# babyNamer.net
KiCad netlist of a schematic drawn in EAGLE
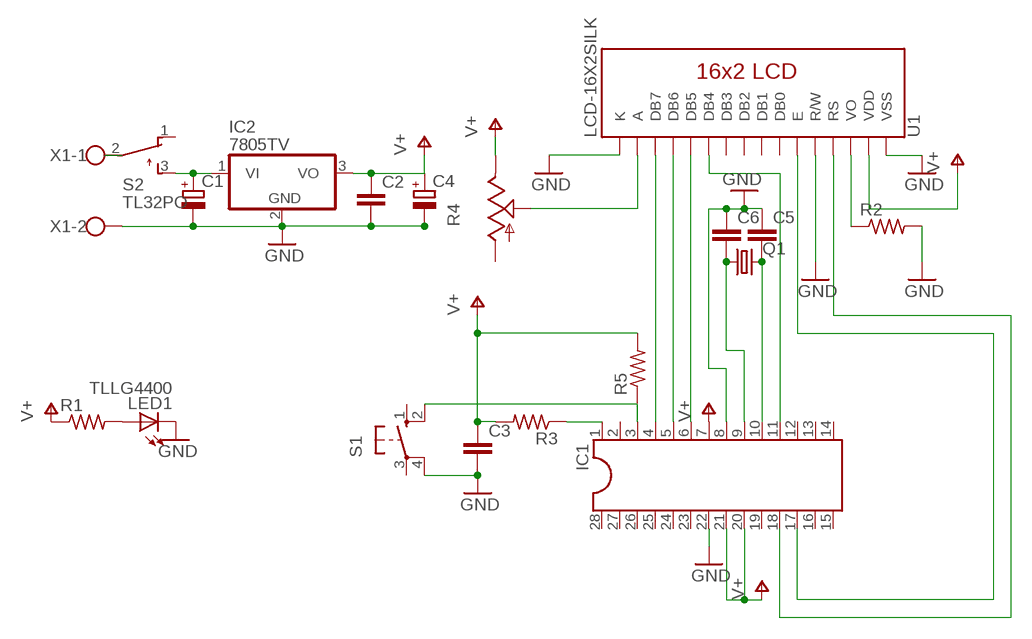
[diagram p0: schematic, sheet 1]

(export (version "E")
  (design (tool "Eeschema 10.0.6"))
  (components
    (comp (ref "C1")
      (value "CPOL-EUE3.5-8")
      (footprint "eagle-import:E3,5-8")
      (libsource (lib "eagle-import") (part "CPOL-EUE3.5-8"))
    )
    (comp (ref "C2")
      (value "C-EU050-024X044")
      (footprint "eagle-import:C050-024X044")
      (libsource (lib "eagle-import") (part "C-EU050-024X044"))
    )
    (comp (ref "C3")
      (value "C-EU050-024X044")
      (footprint "eagle-import:C050-024X044")
      (libsource (lib "eagle-import") (part "C-EU050-024X044"))
    )
    (comp (ref "C4")
      (value "CPOL-EUE3.5-8")
      (footprint "eagle-import:E3,5-8")
      (libsource (lib "eagle-import") (part "CPOL-EUE3.5-8"))
    )
    (comp (ref "C5")
      (value "C-EU050-024X044")
      (footprint "eagle-import:C050-024X044")
      (libsource (lib "eagle-import") (part "C-EU050-024X044"))
    )
    (comp (ref "C6")
      (value "C-EU050-024X044")
      (footprint "eagle-import:C050-024X044")
      (libsource (lib "eagle-import") (part "C-EU050-024X044"))
    )
    (comp (ref "IC1")
      (value "DIL28-3")
      (footprint "eagle-import:DIL28-3")
      (libsource (lib "eagle-import") (part "DIL28-3"))
    )
    (comp (ref "IC2")
      (value "7805TV")
      (footprint "eagle-import:TO220V")
      (libsource (lib "eagle-import") (part "78TV05"))
    )
    (comp (ref "LED1")
      (value "TLLG4400")
      (footprint "eagle-import:LED3MM")
      (fields (field (name "MF") "VISHAY SEMICONDUCTOR"))
      (libsource (lib "eagle-import") (part "TLLG4400"))
    )
    (comp (ref "Q1")
      (value "CRYSTALHC49US")
      (footprint "eagle-import:HC49US")
      (libsource (lib "eagle-import") (part "CRYSTALHC49US"))
    )
    (comp (ref "R1")
      (value "R-US_0204/7")
      (footprint "eagle-import:0204_7")
      (libsource (lib "eagle-import") (part "R-US_0204/7"))
    )
    (comp (ref "R2")
      (value "R-US_0204/7")
      (footprint "eagle-import:0204_7")
      (libsource (lib "eagle-import") (part "R-US_0204/7"))
    )
    (comp (ref "R3")
      (value "R-US_0204/7")
      (footprint "eagle-import:0204_7")
      (libsource (lib "eagle-import") (part "R-US_0204/7"))
    )
    (comp (ref "R4")
      (value "TRIM_US-CA9V")
      (footprint "eagle-import:CA9V")
      (libsource (lib "eagle-import") (part "TRIM_US-CA9V"))
    )
    (comp (ref "R5")
      (value "R-US_0204/7")
      (footprint "eagle-import:0204_7")
      (libsource (lib "eagle-import") (part "R-US_0204/7"))
    )
    (comp (ref "S1")
      (value "10-XX")
      (footprint "eagle-import:B3F-10XX")
      (fields (field (name "MPN") "B3F-1000"))
      (libsource (lib "eagle-import") (part "10-XX"))
    )
    (comp (ref "S2")
      (value "TL32PO")
      (footprint "eagle-import:TL3XPO")
      (libsource (lib "eagle-import") (part "TL32PO"))
    )
    (comp (ref "U1")
      (value "LCD-16X2SILK")
      (footprint "eagle-import:LCD-16X2")
      (libsource (lib "eagle-import") (part "LCD-16X2SILK"))
    )
    (comp (ref "X1")
      (value "W237-102")
      (footprint "eagle-import:W237-102")
      (fields (field (name "MPN") "237-102"))
      (libsource (lib "eagle-import") (part "W237-102"))
    )
  )
  (nets
    (net (code "1") (name "GND") (class "Default")
      (node (ref "C1") (pin "-") (pinfunction "-_-") (pintype "passive"))
      (node (ref "C2") (pin "2") (pinfunction "2_2") (pintype "passive"))
      (node (ref "C3") (pin "2") (pinfunction "2_2") (pintype "passive"))
      (node (ref "C4") (pin "-") (pinfunction "-_-") (pintype "passive"))
      (node (ref "C5") (pin "1") (pinfunction "1_1") (pintype "passive"))
      (node (ref "C6") (pin "1") (pinfunction "1_1") (pintype "passive"))
      (node (ref "IC1") (pin "22") (pinfunction "22_22") (pintype "passive"))
      (node (ref "IC1") (pin "8") (pinfunction "8_8") (pintype "passive"))
      (node (ref "IC2") (pin "2") (pinfunction "GND_2") (pintype "passive"))
      (node (ref "LED1") (pin "K") (pinfunction "C_K") (pintype "passive"))
      (node (ref "R2") (pin "2") (pinfunction "2_2") (pintype "passive"))
      (node (ref "S1") (pin "4") (pinfunction "P1_4") (pintype "passive"))
      (node (ref "U1") (pin "1") (pinfunction "VSS_1") (pintype "power_in"))
      (node (ref "U1") (pin "16") (pinfunction "K_16") (pintype "power_in"))
      (node (ref "U1") (pin "5") (pinfunction "R/W_5") (pintype "input"))
      (node (ref "X1") (pin "2") (pinfunction "KL_2") (pintype "passive"))
    )
    (net (code "2") (name "Net-(C5-Pad2)") (class "Default")
      (node (ref "C5") (pin "2") (pinfunction "2_2") (pintype "passive"))
      (node (ref "IC1") (pin "10") (pinfunction "10_10") (pintype "passive"))
      (node (ref "Q1") (pin "2") (pinfunction "2_2") (pintype "passive"))
    )
    (net (code "3") (name "Net-(C6-Pad2)") (class "Default")
      (node (ref "C6") (pin "2") (pinfunction "2_2") (pintype "passive"))
      (node (ref "IC1") (pin "9") (pinfunction "9_9") (pintype "passive"))
      (node (ref "Q1") (pin "1") (pinfunction "1_1") (pintype "passive"))
    )
    (net (code "4") (name "Net-(IC1-Pad1)") (class "Default")
      (node (ref "IC1") (pin "1") (pinfunction "1_1") (pintype "passive"))
      (node (ref "R3") (pin "1") (pinfunction "1_1") (pintype "passive"))
    )
    (net (code "5") (name "Net-(IC2-VI)") (class "Default")
      (node (ref "C1") (pin "+") (pinfunction "+_+") (pintype "passive"))
      (node (ref "IC2") (pin "1") (pinfunction "VI_1") (pintype "input"))
      (node (ref "S2") (pin "3") (pinfunction "S_3") (pintype "passive"))
    )
    (net (code "6") (name "Net-(LED1-PadA)") (class "Default")
      (node (ref "LED1") (pin "A") (pinfunction "A_A") (pintype "passive"))
      (node (ref "R1") (pin "2") (pinfunction "2_2") (pintype "passive"))
    )
    (net (code "7") (name "Net-(S1-S1)") (class "Default")
      (node (ref "IC1") (pin "3") (pinfunction "3_3") (pintype "passive"))
      (node (ref "R5") (pin "1") (pinfunction "1_1") (pintype "passive"))
      (node (ref "S1") (pin "2") (pinfunction "S1_2") (pintype "passive"))
    )
    (net (code "8") (name "Net-(S2-P)") (class "Default")
      (node (ref "S2") (pin "2") (pinfunction "P_2") (pintype "passive"))
      (node (ref "X1") (pin "1") (pinfunction "KL_1") (pintype "passive"))
    )
    (net (code "9") (name "Net-(U1-A)") (class "Default")
      (node (ref "R4") (pin "S") (pinfunction "S_S") (pintype "passive"))
      (node (ref "U1") (pin "15") (pinfunction "A_15") (pintype "power_in"))
    )
    (net (code "10") (name "Net-(U1-DB4)") (class "Default")
      (node (ref "IC1") (pin "11") (pinfunction "11_11") (pintype "passive"))
      (node (ref "U1") (pin "11") (pinfunction "DB4_11") (pintype "bidirectional"))
    )
    (net (code "11") (name "Net-(U1-DB5)") (class "Default")
      (node (ref "IC1") (pin "6") (pinfunction "6_6") (pintype "passive"))
      (node (ref "U1") (pin "12") (pinfunction "DB5_12") (pintype "bidirectional"))
    )
    (net (code "12") (name "Net-(U1-DB6)") (class "Default")
      (node (ref "IC1") (pin "5") (pinfunction "5_5") (pintype "passive"))
      (node (ref "U1") (pin "13") (pinfunction "DB6_13") (pintype "bidirectional"))
    )
    (net (code "13") (name "Net-(U1-DB7)") (class "Default")
      (node (ref "IC1") (pin "4") (pinfunction "4_4") (pintype "passive"))
      (node (ref "U1") (pin "14") (pinfunction "DB7_14") (pintype "bidirectional"))
    )
    (net (code "14") (name "Net-(U1-E)") (class "Default")
      (node (ref "IC1") (pin "17") (pinfunction "17_17") (pintype "passive"))
      (node (ref "U1") (pin "6") (pinfunction "E_6") (pintype "input"))
    )
    (net (code "15") (name "Net-(U1-RS)") (class "Default")
      (node (ref "IC1") (pin "18") (pinfunction "18_18") (pintype "passive"))
      (node (ref "U1") (pin "4") (pinfunction "RS_4") (pintype "input"))
    )
    (net (code "16") (name "Net-(U1-VO)") (class "Default")
      (node (ref "R2") (pin "1") (pinfunction "1_1") (pintype "passive"))
      (node (ref "U1") (pin "3") (pinfunction "VO_3") (pintype "bidirectional"))
    )
    (net (code "17") (name "V+") (class "Default")
      (node (ref "C2") (pin "1") (pinfunction "1_1") (pintype "passive"))
      (node (ref "C3") (pin "1") (pinfunction "1_1") (pintype "passive"))
      (node (ref "C4") (pin "+") (pinfunction "+_+") (pintype "passive"))
      (node (ref "IC1") (pin "20") (pinfunction "20_20") (pintype "passive"))
      (node (ref "IC1") (pin "21") (pinfunction "21_21") (pintype "passive"))
      (node (ref "IC1") (pin "7") (pinfunction "7_7") (pintype "passive"))
      (node (ref "IC2") (pin "3") (pinfunction "VO_3") (pintype "passive"))
      (node (ref "R1") (pin "1") (pinfunction "1_1") (pintype "passive"))
      (node (ref "R3") (pin "2") (pinfunction "2_2") (pintype "passive"))
      (node (ref "R4") (pin "E") (pinfunction "E_E") (pintype "passive"))
      (node (ref "R5") (pin "2") (pinfunction "2_2") (pintype "passive"))
      (node (ref "U1") (pin "2") (pinfunction "VDD_2") (pintype "power_in"))
    )
    (net (code "18") (name "unconnected-(IC1-Pad2)") (class "Default")
      (node (ref "IC1") (pin "2") (pinfunction "2_2") (pintype "passive"))
    )
    (net (code "19") (name "unconnected-(IC1-Pad12)") (class "Default")
      (node (ref "IC1") (pin "12") (pinfunction "12_12") (pintype "passive"))
    )
    (net (code "20") (name "unconnected-(IC1-Pad13)") (class "Default")
      (node (ref "IC1") (pin "13") (pinfunction "13_13") (pintype "passive"))
    )
    (net (code "21") (name "unconnected-(IC1-Pad14)") (class "Default")
      (node (ref "IC1") (pin "14") (pinfunction "14_14") (pintype "passive"))
    )
    (net (code "22") (name "unconnected-(IC1-Pad15)") (class "Default")
      (node (ref "IC1") (pin "15") (pinfunction "15_15") (pintype "passive"))
    )
    (net (code "23") (name "unconnected-(IC1-Pad16)") (class "Default")
      (node (ref "IC1") (pin "16") (pinfunction "16_16") (pintype "passive"))
    )
    (net (code "24") (name "unconnected-(IC1-Pad19)") (class "Default")
      (node (ref "IC1") (pin "19") (pinfunction "19_19") (pintype "passive"))
    )
    (net (code "25") (name "unconnected-(IC1-Pad23)") (class "Default")
      (node (ref "IC1") (pin "23") (pinfunction "23_23") (pintype "passive"))
    )
    (net (code "26") (name "unconnected-(IC1-Pad24)") (class "Default")
      (node (ref "IC1") (pin "24") (pinfunction "24_24") (pintype "passive"))
    )
    (net (code "27") (name "unconnected-(IC1-Pad25)") (class "Default")
      (node (ref "IC1") (pin "25") (pinfunction "25_25") (pintype "passive"))
    )
    (net (code "28") (name "unconnected-(IC1-Pad26)") (class "Default")
      (node (ref "IC1") (pin "26") (pinfunction "26_26") (pintype "passive"))
    )
    (net (code "29") (name "unconnected-(IC1-Pad27)") (class "Default")
      (node (ref "IC1") (pin "27") (pinfunction "27_27") (pintype "passive"))
    )
    (net (code "30") (name "unconnected-(IC1-Pad28)") (class "Default")
      (node (ref "IC1") (pin "28") (pinfunction "28_28") (pintype "passive"))
    )
    (net (code "31") (name "unconnected-(R4-PadA)") (class "Default")
      (node (ref "R4") (pin "A") (pinfunction "A_A") (pintype "passive"))
    )
    (net (code "32") (name "unconnected-(S1-P-Pad3)") (class "Default")
      (node (ref "S1") (pin "3") (pinfunction "P_3") (pintype "passive"))
    )
    (net (code "33") (name "unconnected-(S1-S-Pad1)") (class "Default")
      (node (ref "S1") (pin "1") (pinfunction "S_1") (pintype "passive"))
    )
    (net (code "34") (name "unconnected-(S2-O-Pad1)") (class "Default")
      (node (ref "S2") (pin "1") (pinfunction "O_1") (pintype "passive"))
    )
    (net (code "35") (name "unconnected-(U1-DB0-Pad7)") (class "Default")
      (node (ref "U1") (pin "7") (pinfunction "DB0_7") (pintype "bidirectional"))
    )
    (net (code "36") (name "unconnected-(U1-DB1-Pad8)") (class "Default")
      (node (ref "U1") (pin "8") (pinfunction "DB1_8") (pintype "bidirectional"))
    )
    (net (code "37") (name "unconnected-(U1-DB2-Pad9)") (class "Default")
      (node (ref "U1") (pin "9") (pinfunction "DB2_9") (pintype "bidirectional"))
    )
    (net (code "38") (name "unconnected-(U1-DB3-Pad10)") (class "Default")
      (node (ref "U1") (pin "10") (pinfunction "DB3_10") (pintype "bidirectional"))
    )
  )
)
